# Connectors.net
KiCad netlist of a schematic drawn in Altium Designer
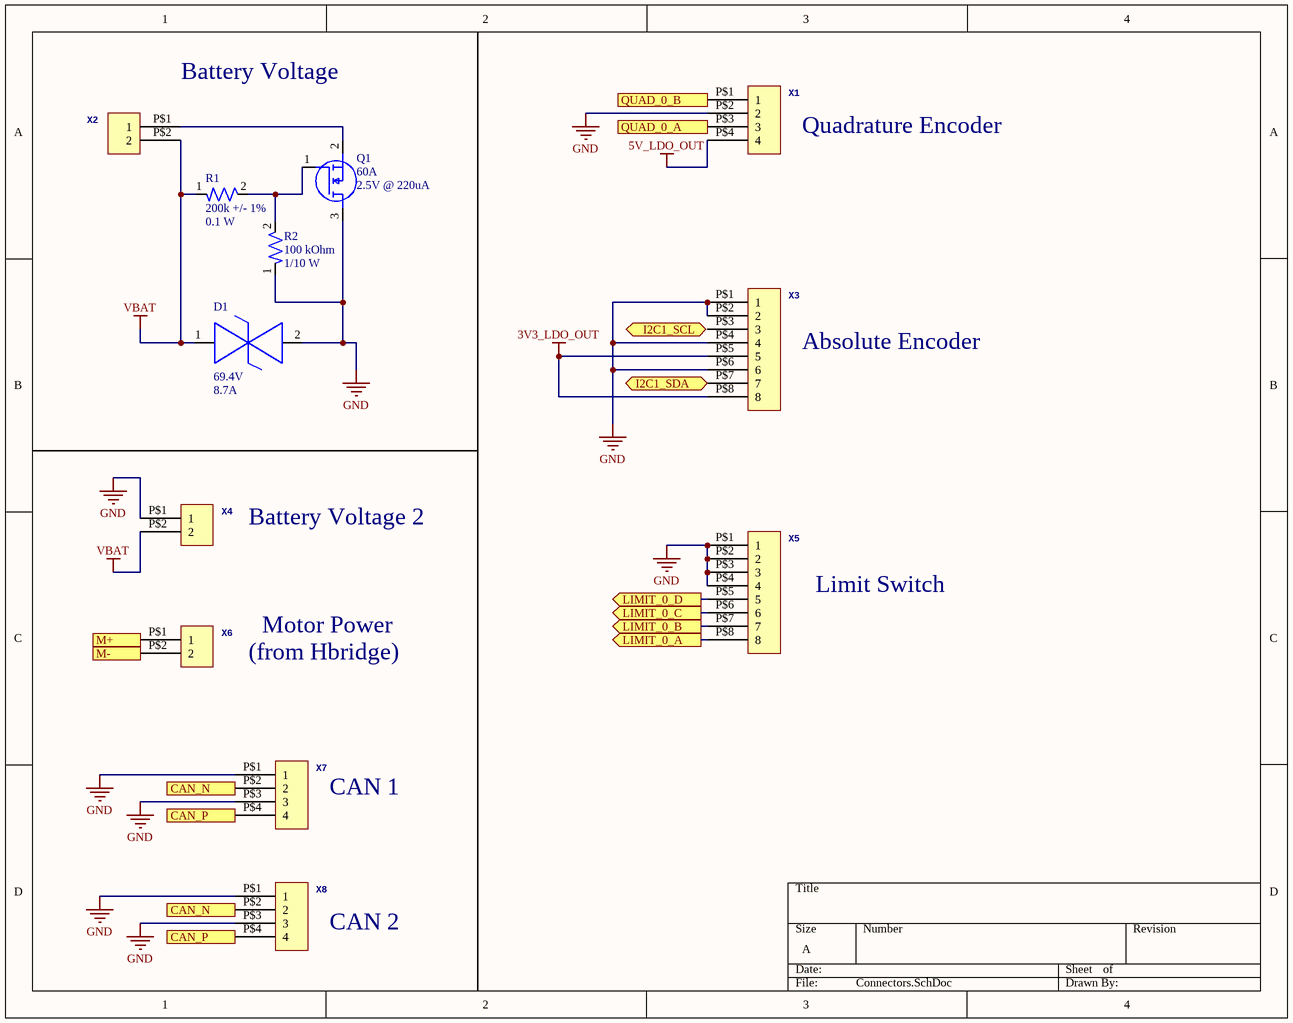
[diagram p0: Connectors.SchDoc]

(export (version "E")
  (design (tool "Eeschema 10.0.6"))
  (components
    (comp (ref "D1")
      (value "SMBJE43CAH")
      (footprint "DO-214AA (SMBJ)")
      (description "69.4V Clamp 8.7A Ipp Tvs Diode Surface Mount DO-214AA (SMBJ)")
      (fields (field (name "VCLAMP") "69.4V") (field (name "PEAK PULSER CURRENT") "8.7A"))
      (libsource (lib "MasterLib") (part "DIO-69.4V-0001"))
    )
    (comp (ref "Q1")
      (value "TPH7R006PL,L1Q")
      (footprint "NMOS-8PowerVDFN")
      (description "N-Channel 60 V 60A (Tc) 81W (Tc) Surface Mount 8-SOP Advance (5x5)")
      (fields (field (name "DRAIN CURRENT") "60A") (field (name "VGS") "2.5V @ 220uA"))
      (libsource (lib "MasterLib") (part "NMOS-60A-0001"))
    )
    (comp (ref "R1")
      (value "ERJ-3EKF2003V")
      (footprint "RES-0603")
      (description "200 kOhms ±1% 0.1W, 1/10W Chip Resistor 0603 (1608 Metric) Automotive AEC-Q200 Thick Film")
      (fields
        (field (name "MANUFACTURER") "Panasonic Electronic Components")
        (field (name "RESISTANCE") "200k +/- 1%")
        (field (name "POWER RATING") "0.1 W")
      )
      (libsource (lib "MasterLib") (part "RES-200K-0001"))
    )
    (comp (ref "R2")
      (value "RC0603FR-07100KL")
      (footprint "RES-0603")
      (description "100 kOhms ±1% 0.1W, 1/10W Chip Resistor 0603 (1608 Metric) Moisture Resistant Thick Film")
      (fields
        (field (name "TOLERANCE") "+/- 1%")
        (field (name "RESISTANCE") "100 kOhm")
        (field (name "POWER") "1/10 W")
      )
      (libsource (lib "MasterLib") (part "RES-100K-0003"))
    )
    (comp (ref "X1")
      (value "Molex 43045-0412")
      (footprint "43045-0412")
      (libsource (lib "Molex Microfit") (part "Micro-Fit Molex 4 Pin 2 Row Vertical"))
    )
    (comp (ref "X2")
      (value "Molex 43650-0215")
      (footprint "43650-0215")
      (libsource (lib "") (part "Micro-Fit Molex 2 Pin Vertical_1"))
    )
    (comp (ref "X3")
      (value "Molex 43045-0812")
      (footprint "43045-0812")
      (libsource (lib "Molex Microfit") (part "Micro-Fit Molex 8 Pin 2 Row Vertical"))
    )
    (comp (ref "X4")
      (value "Molex 43650-0215")
      (footprint "43650-0215")
      (libsource (lib "Molex Microfit") (part "Micro-Fit Molex 2 Pin Vertical"))
    )
    (comp (ref "X5")
      (value "Molex 43045-0812")
      (footprint "43045-0812")
      (libsource (lib "Molex Microfit") (part "Micro-Fit Molex 8 Pin 2 Row Vertical"))
    )
    (comp (ref "X6")
      (value "Molex 43650-0215")
      (footprint "43650-0215")
      (libsource (lib "Molex Microfit") (part "Micro-Fit Molex 2 Pin Vertical"))
    )
    (comp (ref "X7")
      (value "Molex 43045-0412")
      (footprint "43045-0412")
      (libsource (lib "Molex Microfit") (part "Micro-Fit Molex 4 Pin 2 Row Vertical"))
    )
    (comp (ref "X8")
      (value "Molex 43045-0412")
      (footprint "43045-0412")
      (libsource (lib "Molex Microfit") (part "Micro-Fit Molex 4 Pin 2 Row Vertical"))
    )
  )
  (nets
    (net (code "1") (name "/CAN_N") (class "Default")
      (node (ref "X7") (pin "P$2") (pinfunction "2_P$2") (pintype "passive"))
      (node (ref "X8") (pin "P$2") (pinfunction "2_P$2") (pintype "passive"))
    )
    (net (code "2") (name "/CAN_P") (class "Default")
      (node (ref "X7") (pin "P$4") (pinfunction "4_P$4") (pintype "passive"))
      (node (ref "X8") (pin "P$4") (pinfunction "4_P$4") (pintype "passive"))
    )
    (net (code "4") (name "/I2C1_SDA") (class "Default")
      (node (ref "X3") (pin "P$7") (pinfunction "7_P$7") (pintype "passive"))
    )
    (net (code "5") (name "/LIMIT_0_A") (class "Default")
      (node (ref "X5") (pin "P$8") (pinfunction "8_P$8") (pintype "passive"))
    )
    (net (code "6") (name "/LIMIT_0_B") (class "Default")
      (node (ref "X5") (pin "P$7") (pinfunction "7_P$7") (pintype "passive"))
    )
    (net (code "7") (name "/LIMIT_0_C") (class "Default")
      (node (ref "X5") (pin "P$6") (pinfunction "6_P$6") (pintype "passive"))
    )
    (net (code "8") (name "/LIMIT_0_D") (class "Default")
      (node (ref "X5") (pin "P$5") (pinfunction "5_P$5") (pintype "passive"))
    )
    (net (code "9") (name "/M+") (class "Default")
      (node (ref "X6") (pin "P$1") (pinfunction "1_P$1") (pintype "passive"))
    )
    (net (code "10") (name "/M-") (class "Default")
      (node (ref "X6") (pin "P$2") (pinfunction "2_P$2") (pintype "passive"))
    )
    (net (code "11") (name "/QUAD_0_A") (class "Default")
      (node (ref "X1") (pin "P$3") (pinfunction "3_P$3") (pintype "passive"))
    )
    (net (code "12") (name "/QUAD_0_B") (class "Default")
      (node (ref "X1") (pin "P$1") (pinfunction "1_P$1") (pintype "passive"))
    )
    (net (code "13") (name "3V3_LDO_OUT") (class "Default")
      (node (ref "X3") (pin "P$5") (pinfunction "5_P$5") (pintype "passive"))
      (node (ref "X3") (pin "P$8") (pinfunction "8_P$8") (pintype "passive"))
    )
    (net (code "14") (name "5V_LDO_OUT") (class "Default")
      (node (ref "X1") (pin "P$4") (pinfunction "4_P$4") (pintype "passive"))
    )
    (net (code "15") (name "GND") (class "Default")
      (node (ref "D1") (pin "2") (pintype "passive"))
      (node (ref "Q1") (pin "3") (pinfunction "D_3") (pintype "passive"))
      (node (ref "R2") (pin "1") (pinfunction "1_1") (pintype "passive"))
      (node (ref "X1") (pin "P$2") (pinfunction "2_P$2") (pintype "passive"))
      (node (ref "X3") (pin "P$1") (pinfunction "1_P$1") (pintype "passive"))
      (node (ref "X3") (pin "P$2") (pinfunction "2_P$2") (pintype "passive"))
      (node (ref "X3") (pin "P$4") (pinfunction "4_P$4") (pintype "passive"))
      (node (ref "X3") (pin "P$6") (pinfunction "6_P$6") (pintype "passive"))
      (node (ref "X4") (pin "P$1") (pinfunction "1_P$1") (pintype "passive"))
      (node (ref "X5") (pin "P$1") (pinfunction "1_P$1") (pintype "passive"))
      (node (ref "X5") (pin "P$2") (pinfunction "2_P$2") (pintype "passive"))
      (node (ref "X5") (pin "P$3") (pinfunction "3_P$3") (pintype "passive"))
      (node (ref "X5") (pin "P$4") (pinfunction "4_P$4") (pintype "passive"))
      (node (ref "X7") (pin "P$1") (pinfunction "1_P$1") (pintype "passive"))
      (node (ref "X7") (pin "P$3") (pinfunction "3_P$3") (pintype "passive"))
      (node (ref "X8") (pin "P$1") (pinfunction "1_P$1") (pintype "passive"))
      (node (ref "X8") (pin "P$3") (pinfunction "3_P$3") (pintype "passive"))
    )
    (net (code "16") (name "Net-(Q1-G)") (class "Default")
      (node (ref "Q1") (pin "1") (pinfunction "G_1") (pintype "passive"))
      (node (ref "R1") (pin "2") (pinfunction "2_2") (pintype "passive"))
      (node (ref "R2") (pin "2") (pinfunction "2_2") (pintype "passive"))
    )
    (net (code "17") (name "Net-(Q1-S)") (class "Default")
      (node (ref "Q1") (pin "2") (pinfunction "S_2") (pintype "passive"))
      (node (ref "X2") (pin "P$1") (pinfunction "1_P$1") (pintype "passive"))
    )
    (net (code "18") (name "VBAT") (class "Default")
      (node (ref "D1") (pin "1") (pintype "passive"))
      (node (ref "R1") (pin "1") (pinfunction "1_1") (pintype "passive"))
      (node (ref "X2") (pin "P$2") (pinfunction "2_P$2") (pintype "passive"))
      (node (ref "X4") (pin "P$2") (pinfunction "2_P$2") (pintype "passive"))
    )
    (net (code "19") (name "unconnected-(X3-3-PadP$3)") (class "Default")
      (node (ref "X3") (pin "P$3") (pinfunction "3_P$3") (pintype "passive"))
    )
  )
)
